# heater_control.net
KiCad netlist of a schematic drawn in Altium Designer
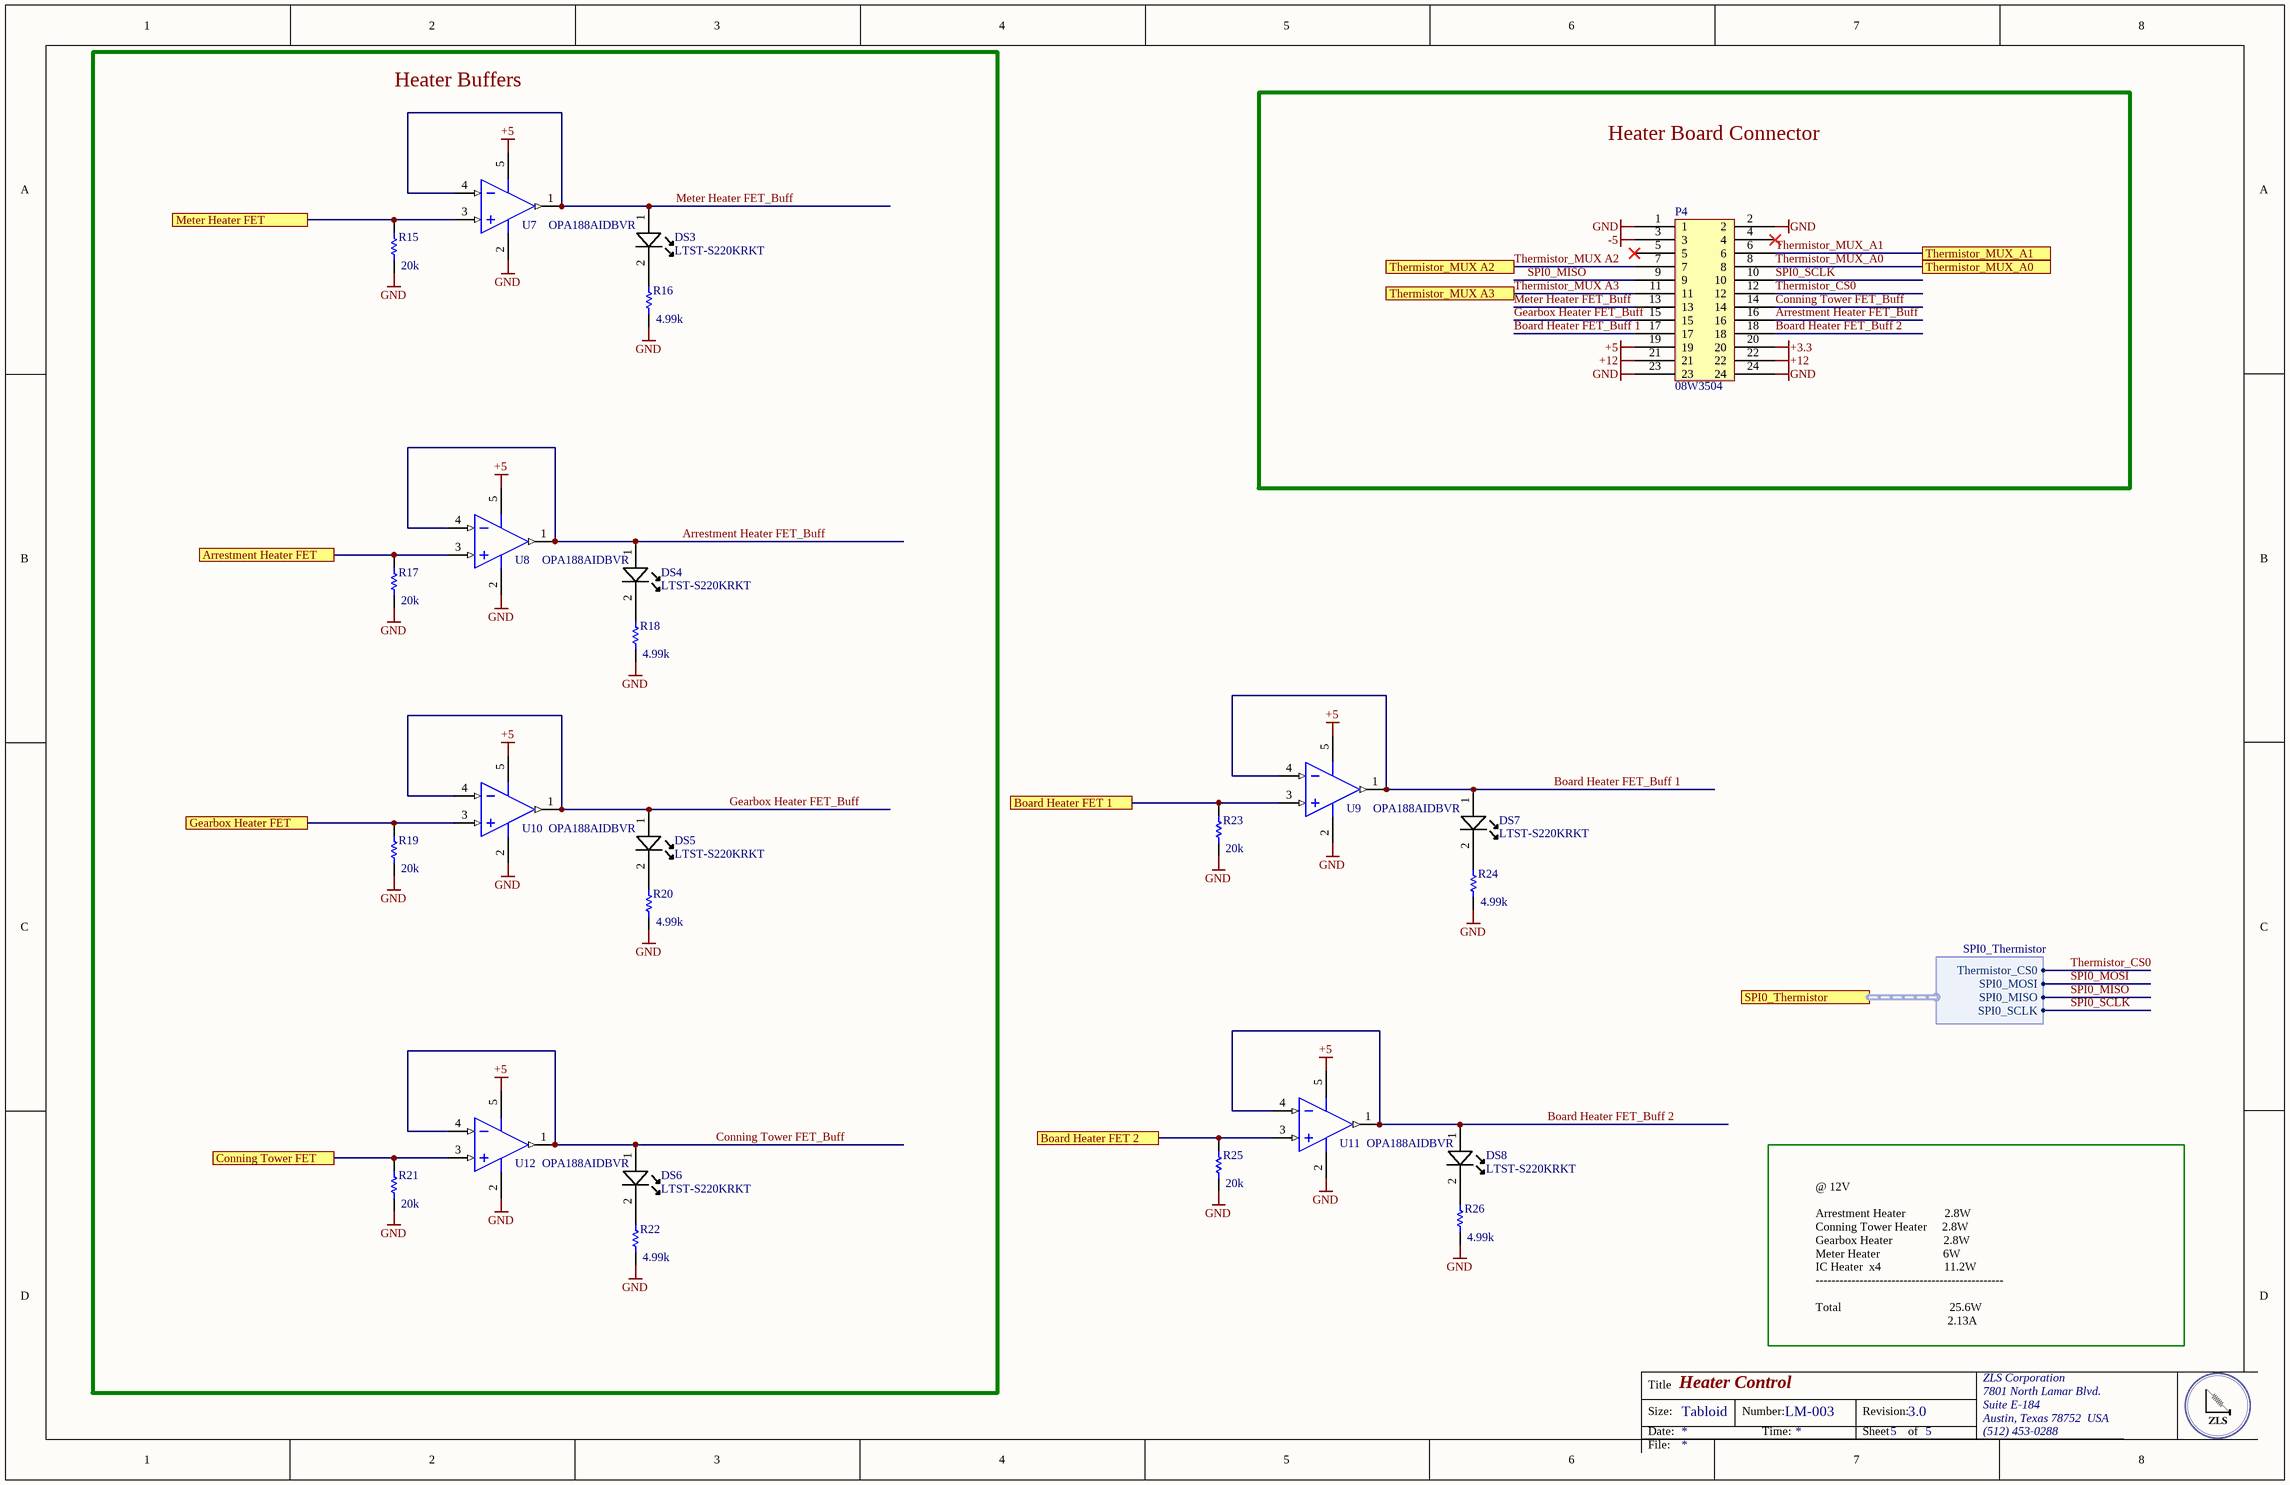
[diagram p0: heater_control.SchDoc]

(export (version "E")
  (design (tool "Eeschema 10.0.6"))
  (components
    (comp (ref "DS3")
      (value "Visible Name Value Type    False Description Lite-On LTST-S220KRKT Red LED, 631 nm 2012 (0805) Side View, Rectangle Lens SMD package STRING")
      (footprint "0805C_L")
      (fields
        (field (name "MANUFACTURER") "Vishay / Lite-On")
        (field (name "MANUFACTURER PART NUMBER") "LTST-S220KRKT")
      )
      (libsource (lib "*") (part "LED A/K"))
    )
    (comp (ref "DS4")
      (value "Visible Name Value Type    False Description Lite-On LTST-S220KRKT Red LED, 631 nm 2012 (0805) Side View, Rectangle Lens SMD package STRING")
      (footprint "0805C_L")
      (fields
        (field (name "MANUFACTURER") "Vishay / Lite-On")
        (field (name "MANUFACTURER PART NUMBER") "LTST-S220KRKT")
      )
      (libsource (lib "*") (part "LED A/K"))
    )
    (comp (ref "DS5")
      (value "Visible Name Value Type    False Description Lite-On LTST-S220KRKT Red LED, 631 nm 2012 (0805) Side View, Rectangle Lens SMD package STRING")
      (footprint "0805C_L")
      (fields
        (field (name "MANUFACTURER") "Vishay / Lite-On")
        (field (name "MANUFACTURER PART NUMBER") "LTST-S220KRKT")
      )
      (libsource (lib "*") (part "LED A/K"))
    )
    (comp (ref "DS6")
      (value "Visible Name Value Type    False Description Lite-On LTST-S220KRKT Red LED, 631 nm 2012 (0805) Side View, Rectangle Lens SMD package STRING")
      (footprint "0805C_L")
      (fields
        (field (name "MANUFACTURER") "Vishay / Lite-On")
        (field (name "MANUFACTURER PART NUMBER") "LTST-S220KRKT")
      )
      (libsource (lib "*") (part "LED A/K"))
    )
    (comp (ref "DS7")
      (value "Visible Name Value Type    False Description Lite-On LTST-S220KRKT Red LED, 631 nm 2012 (0805) Side View, Rectangle Lens SMD package STRING")
      (footprint "0805C_L")
      (fields
        (field (name "MANUFACTURER") "Vishay / Lite-On")
        (field (name "MANUFACTURER PART NUMBER") "LTST-S220KRKT")
      )
      (libsource (lib "*") (part "LED A/K"))
    )
    (comp (ref "DS8")
      (value "Visible Name Value Type    False Description Lite-On LTST-S220KRKT Red LED, 631 nm 2012 (0805) Side View, Rectangle Lens SMD package STRING")
      (footprint "0805C_L")
      (fields
        (field (name "MANUFACTURER") "Vishay / Lite-On")
        (field (name "MANUFACTURER PART NUMBER") "LTST-S220KRKT")
      )
      (libsource (lib "*") (part "LED A/K"))
    )
    (comp (ref "P4")
      (value "IPL1-112-01-F-S-K")
      (footprint "IPL1-112-01-F-S-K")
      (description "IPL1-112-01-F-D-K")
      (fields (field (name "SUPPLIER PART NUMBER 1") "08W3504"))
      (libsource (lib "ZLS_Schematic_lib") (part "IPL1-112-01-F-S-K"))
    )
    (comp (ref "R15")
      (value "20k")
      (footprint "RESC0402(1005)_M")
      (libsource (lib "Altium Content Vault") (part "CMP-1011-00651-1"))
    )
    (comp (ref "R16")
      (value "4.99k")
      (footprint "RESC0402(1005)_M")
      (libsource (lib "Altium Content Vault") (part "CMP-1011-00651-1"))
    )
    (comp (ref "R17")
      (value "20k")
      (footprint "RESC0402(1005)_M")
      (libsource (lib "Altium Content Vault") (part "CMP-1011-00651-1"))
    )
    (comp (ref "R18")
      (value "4.99k")
      (footprint "RESC0402(1005)_M")
      (libsource (lib "Altium Content Vault") (part "CMP-1011-00651-1"))
    )
    (comp (ref "R19")
      (value "20k")
      (footprint "RESC0402(1005)_M")
      (libsource (lib "Altium Content Vault") (part "CMP-1011-00651-1"))
    )
    (comp (ref "R20")
      (value "4.99k")
      (footprint "RESC0402(1005)_M")
      (libsource (lib "Altium Content Vault") (part "CMP-1011-00651-1"))
    )
    (comp (ref "R21")
      (value "20k")
      (footprint "RESC0402(1005)_M")
      (libsource (lib "Altium Content Vault") (part "CMP-1011-00651-1"))
    )
    (comp (ref "R22")
      (value "4.99k")
      (footprint "RESC0402(1005)_M")
      (libsource (lib "Altium Content Vault") (part "CMP-1011-00651-1"))
    )
    (comp (ref "R23")
      (value "20k")
      (footprint "RESC0402(1005)_M")
      (libsource (lib "Altium Content Vault") (part "CMP-1011-00651-1"))
    )
    (comp (ref "R24")
      (value "4.99k")
      (footprint "RESC0402(1005)_M")
      (libsource (lib "Altium Content Vault") (part "CMP-1011-00651-1"))
    )
    (comp (ref "R25")
      (value "20k")
      (footprint "RESC0402(1005)_M")
      (libsource (lib "Altium Content Vault") (part "CMP-1011-00651-1"))
    )
    (comp (ref "R26")
      (value "4.99k")
      (footprint "RESC0402(1005)_M")
      (libsource (lib "Altium Content Vault") (part "CMP-1011-00651-1"))
    )
    (comp (ref "U7")
      (value "OPA188AIDBVR")
      (footprint "DBV0005A_M")
      (fields (field (name "MANUFACTURER") "Texas Instruments"))
      (libsource (lib "Altium Content Vault") (part "CMP-0809-00005-2"))
    )
    (comp (ref "U8")
      (value "OPA188AIDBVR")
      (footprint "DBV0005A_M")
      (fields (field (name "MANUFACTURER") "Texas Instruments"))
      (libsource (lib "Altium Content Vault") (part "CMP-0809-00005-2"))
    )
    (comp (ref "U9")
      (value "OPA188AIDBVR")
      (footprint "DBV0005A_M")
      (fields (field (name "MANUFACTURER") "Texas Instruments"))
      (libsource (lib "Altium Content Vault") (part "CMP-0809-00005-2"))
    )
    (comp (ref "U10")
      (value "OPA188AIDBVR")
      (footprint "DBV0005A_M")
      (fields (field (name "MANUFACTURER") "Texas Instruments"))
      (libsource (lib "Altium Content Vault") (part "CMP-0809-00005-2"))
    )
    (comp (ref "U11")
      (value "OPA188AIDBVR")
      (footprint "DBV0005A_M")
      (fields (field (name "MANUFACTURER") "Texas Instruments"))
      (libsource (lib "Altium Content Vault") (part "CMP-0809-00005-2"))
    )
    (comp (ref "U12")
      (value "OPA188AIDBVR")
      (footprint "DBV0005A_M")
      (fields (field (name "MANUFACTURER") "Texas Instruments"))
      (libsource (lib "Altium Content Vault") (part "CMP-0809-00005-2"))
    )
  )
  (nets
    (net (code "2") (name "+3.3") (class "Default")
      (node (ref "P4") (pin "20") (pinfunction "20_20") (pintype "passive"))
    )
    (net (code "3") (name "+5") (class "Default")
      (node (ref "P4") (pin "19") (pinfunction "19_19") (pintype "passive"))
      (node (ref "U10") (pin "5") (pinfunction "V+_5") (pintype "power_in"))
      (node (ref "U11") (pin "5") (pinfunction "V+_5") (pintype "power_in"))
      (node (ref "U12") (pin "5") (pinfunction "V+_5") (pintype "power_in"))
      (node (ref "U7") (pin "5") (pinfunction "V+_5") (pintype "power_in"))
      (node (ref "U8") (pin "5") (pinfunction "V+_5") (pintype "power_in"))
      (node (ref "U9") (pin "5") (pinfunction "V+_5") (pintype "power_in"))
    )
    (net (code "4") (name "+12") (class "Default")
      (node (ref "P4") (pin "21") (pinfunction "21_21") (pintype "passive"))
      (node (ref "P4") (pin "22") (pinfunction "22_22") (pintype "passive"))
    )
    (net (code "5") (name "-5") (class "Default")
      (node (ref "P4") (pin "3") (pinfunction "3_3") (pintype "passive"))
    )
    (net (code "6") (name "/Arrestment Heater FET") (class "Default")
      (node (ref "R17") (pin "1") (pinfunction "1_1") (pintype "passive"))
      (node (ref "U8") (pin "3") (pinfunction "IN+_3") (pintype "input"))
    )
    (net (code "7") (name "/Arrestment Heater FET_Buff") (class "Default")
      (node (ref "DS4") (pin "1") (pinfunction "A_1") (pintype "passive"))
      (node (ref "P4") (pin "16") (pinfunction "16_16") (pintype "passive"))
      (node (ref "U8") (pin "1") (pinfunction "OUT_1") (pintype "output"))
      (node (ref "U8") (pin "4") (pinfunction "IN-_4") (pintype "input"))
    )
    (net (code "8") (name "/Board Heater FET 1") (class "Default")
      (node (ref "R23") (pin "1") (pinfunction "1_1") (pintype "passive"))
      (node (ref "U9") (pin "3") (pinfunction "IN+_3") (pintype "input"))
    )
    (net (code "9") (name "/Board Heater FET 2") (class "Default")
      (node (ref "R25") (pin "1") (pinfunction "1_1") (pintype "passive"))
      (node (ref "U11") (pin "3") (pinfunction "IN+_3") (pintype "input"))
    )
    (net (code "10") (name "/Board Heater FET_Buff 1") (class "Default")
      (node (ref "DS7") (pin "1") (pinfunction "A_1") (pintype "passive"))
      (node (ref "P4") (pin "17") (pinfunction "17_17") (pintype "passive"))
      (node (ref "U9") (pin "1") (pinfunction "OUT_1") (pintype "output"))
      (node (ref "U9") (pin "4") (pinfunction "IN-_4") (pintype "input"))
    )
    (net (code "11") (name "/Board Heater FET_Buff 2") (class "Default")
      (node (ref "DS8") (pin "1") (pinfunction "A_1") (pintype "passive"))
      (node (ref "P4") (pin "18") (pinfunction "18_18") (pintype "passive"))
      (node (ref "U11") (pin "1") (pinfunction "OUT_1") (pintype "output"))
      (node (ref "U11") (pin "4") (pinfunction "IN-_4") (pintype "input"))
    )
    (net (code "12") (name "/Conning Tower FET") (class "Default")
      (node (ref "R21") (pin "1") (pinfunction "1_1") (pintype "passive"))
      (node (ref "U12") (pin "3") (pinfunction "IN+_3") (pintype "input"))
    )
    (net (code "13") (name "/Conning Tower FET_Buff") (class "Default")
      (node (ref "DS6") (pin "1") (pinfunction "A_1") (pintype "passive"))
      (node (ref "P4") (pin "14") (pinfunction "14_14") (pintype "passive"))
      (node (ref "U12") (pin "1") (pinfunction "OUT_1") (pintype "output"))
      (node (ref "U12") (pin "4") (pinfunction "IN-_4") (pintype "input"))
    )
    (net (code "14") (name "/Gearbox Heater FET") (class "Default")
      (node (ref "R19") (pin "1") (pinfunction "1_1") (pintype "passive"))
      (node (ref "U10") (pin "3") (pinfunction "IN+_3") (pintype "input"))
    )
    (net (code "15") (name "/Gearbox Heater FET_Buff") (class "Default")
      (node (ref "DS5") (pin "1") (pinfunction "A_1") (pintype "passive"))
      (node (ref "P4") (pin "15") (pinfunction "15_15") (pintype "passive"))
      (node (ref "U10") (pin "1") (pinfunction "OUT_1") (pintype "output"))
      (node (ref "U10") (pin "4") (pinfunction "IN-_4") (pintype "input"))
    )
    (net (code "16") (name "/Meter Heater FET") (class "Default")
      (node (ref "R15") (pin "1") (pinfunction "1_1") (pintype "passive"))
      (node (ref "U7") (pin "3") (pinfunction "IN+_3") (pintype "input"))
    )
    (net (code "17") (name "/Meter Heater FET_Buff") (class "Default")
      (node (ref "DS3") (pin "1") (pinfunction "A_1") (pintype "passive"))
      (node (ref "P4") (pin "13") (pinfunction "13_13") (pintype "passive"))
      (node (ref "U7") (pin "1") (pinfunction "OUT_1") (pintype "output"))
      (node (ref "U7") (pin "4") (pinfunction "IN-_4") (pintype "input"))
    )
    (net (code "18") (name "/SPI0_MISO") (class "Default")
      (node (ref "P4") (pin "9") (pinfunction "9_9") (pintype "passive"))
    )
    (net (code "20") (name "/SPI0_SCLK") (class "Default")
      (node (ref "P4") (pin "10") (pinfunction "10_10") (pintype "passive"))
    )
    (net (code "21") (name "/Thermistor_CS0") (class "Default")
      (node (ref "P4") (pin "12") (pinfunction "12_12") (pintype "passive"))
    )
    (net (code "22") (name "/Thermistor_MUX A2") (class "Default")
      (node (ref "P4") (pin "7") (pinfunction "7_7") (pintype "passive"))
    )
    (net (code "23") (name "/Thermistor_MUX A3") (class "Default")
      (node (ref "P4") (pin "11") (pinfunction "11_11") (pintype "passive"))
    )
    (net (code "24") (name "/Thermistor_MUX_A0") (class "Default")
      (node (ref "P4") (pin "8") (pinfunction "8_8") (pintype "passive"))
    )
    (net (code "25") (name "/Thermistor_MUX_A1") (class "Default")
      (node (ref "P4") (pin "6") (pinfunction "6_6") (pintype "passive"))
    )
    (net (code "27") (name "GND") (class "Default")
      (node (ref "P4") (pin "1") (pinfunction "1_1") (pintype "passive"))
      (node (ref "P4") (pin "2") (pinfunction "2_2") (pintype "passive"))
      (node (ref "P4") (pin "23") (pinfunction "23_23") (pintype "passive"))
      (node (ref "P4") (pin "24") (pinfunction "24_24") (pintype "passive"))
      (node (ref "R15") (pin "2") (pinfunction "2_2") (pintype "passive"))
      (node (ref "R16") (pin "2") (pinfunction "2_2") (pintype "passive"))
      (node (ref "R17") (pin "2") (pinfunction "2_2") (pintype "passive"))
      (node (ref "R18") (pin "2") (pinfunction "2_2") (pintype "passive"))
      (node (ref "R19") (pin "2") (pinfunction "2_2") (pintype "passive"))
      (node (ref "R20") (pin "2") (pinfunction "2_2") (pintype "passive"))
      (node (ref "R21") (pin "2") (pinfunction "2_2") (pintype "passive"))
      (node (ref "R22") (pin "2") (pinfunction "2_2") (pintype "passive"))
      (node (ref "R23") (pin "2") (pinfunction "2_2") (pintype "passive"))
      (node (ref "R24") (pin "2") (pinfunction "2_2") (pintype "passive"))
      (node (ref "R25") (pin "2") (pinfunction "2_2") (pintype "passive"))
      (node (ref "R26") (pin "2") (pinfunction "2_2") (pintype "passive"))
      (node (ref "U10") (pin "2") (pinfunction "V-_2") (pintype "power_in"))
      (node (ref "U11") (pin "2") (pinfunction "V-_2") (pintype "power_in"))
      (node (ref "U12") (pin "2") (pinfunction "V-_2") (pintype "power_in"))
      (node (ref "U7") (pin "2") (pinfunction "V-_2") (pintype "power_in"))
      (node (ref "U8") (pin "2") (pinfunction "V-_2") (pintype "power_in"))
      (node (ref "U9") (pin "2") (pinfunction "V-_2") (pintype "power_in"))
    )
    (net (code "28") (name "Net-(DS3-K)") (class "Default")
      (node (ref "DS3") (pin "2") (pinfunction "K_2") (pintype "passive"))
      (node (ref "R16") (pin "1") (pinfunction "1_1") (pintype "passive"))
    )
    (net (code "29") (name "Net-(DS4-K)") (class "Default")
      (node (ref "DS4") (pin "2") (pinfunction "K_2") (pintype "passive"))
      (node (ref "R18") (pin "1") (pinfunction "1_1") (pintype "passive"))
    )
    (net (code "30") (name "Net-(DS5-K)") (class "Default")
      (node (ref "DS5") (pin "2") (pinfunction "K_2") (pintype "passive"))
      (node (ref "R20") (pin "1") (pinfunction "1_1") (pintype "passive"))
    )
    (net (code "31") (name "Net-(DS6-K)") (class "Default")
      (node (ref "DS6") (pin "2") (pinfunction "K_2") (pintype "passive"))
      (node (ref "R22") (pin "1") (pinfunction "1_1") (pintype "passive"))
    )
    (net (code "32") (name "Net-(DS7-K)") (class "Default")
      (node (ref "DS7") (pin "2") (pinfunction "K_2") (pintype "passive"))
      (node (ref "R24") (pin "1") (pinfunction "1_1") (pintype "passive"))
    )
    (net (code "33") (name "Net-(DS8-K)") (class "Default")
      (node (ref "DS8") (pin "2") (pinfunction "K_2") (pintype "passive"))
      (node (ref "R26") (pin "1") (pinfunction "1_1") (pintype "passive"))
    )
    (net (code "34") (name "unconnected-(P4-Pad4)") (class "Default")
      (node (ref "P4") (pin "4") (pinfunction "4_4") (pintype "passive+no_connect"))
    )
    (net (code "35") (name "unconnected-(P4-Pad5)") (class "Default")
      (node (ref "P4") (pin "5") (pinfunction "5_5") (pintype "passive+no_connect"))
    )
  )
)
